# CNEPuckRevF_Drivers_2.net
KiCad netlist of a schematic drawn in Altium Designer
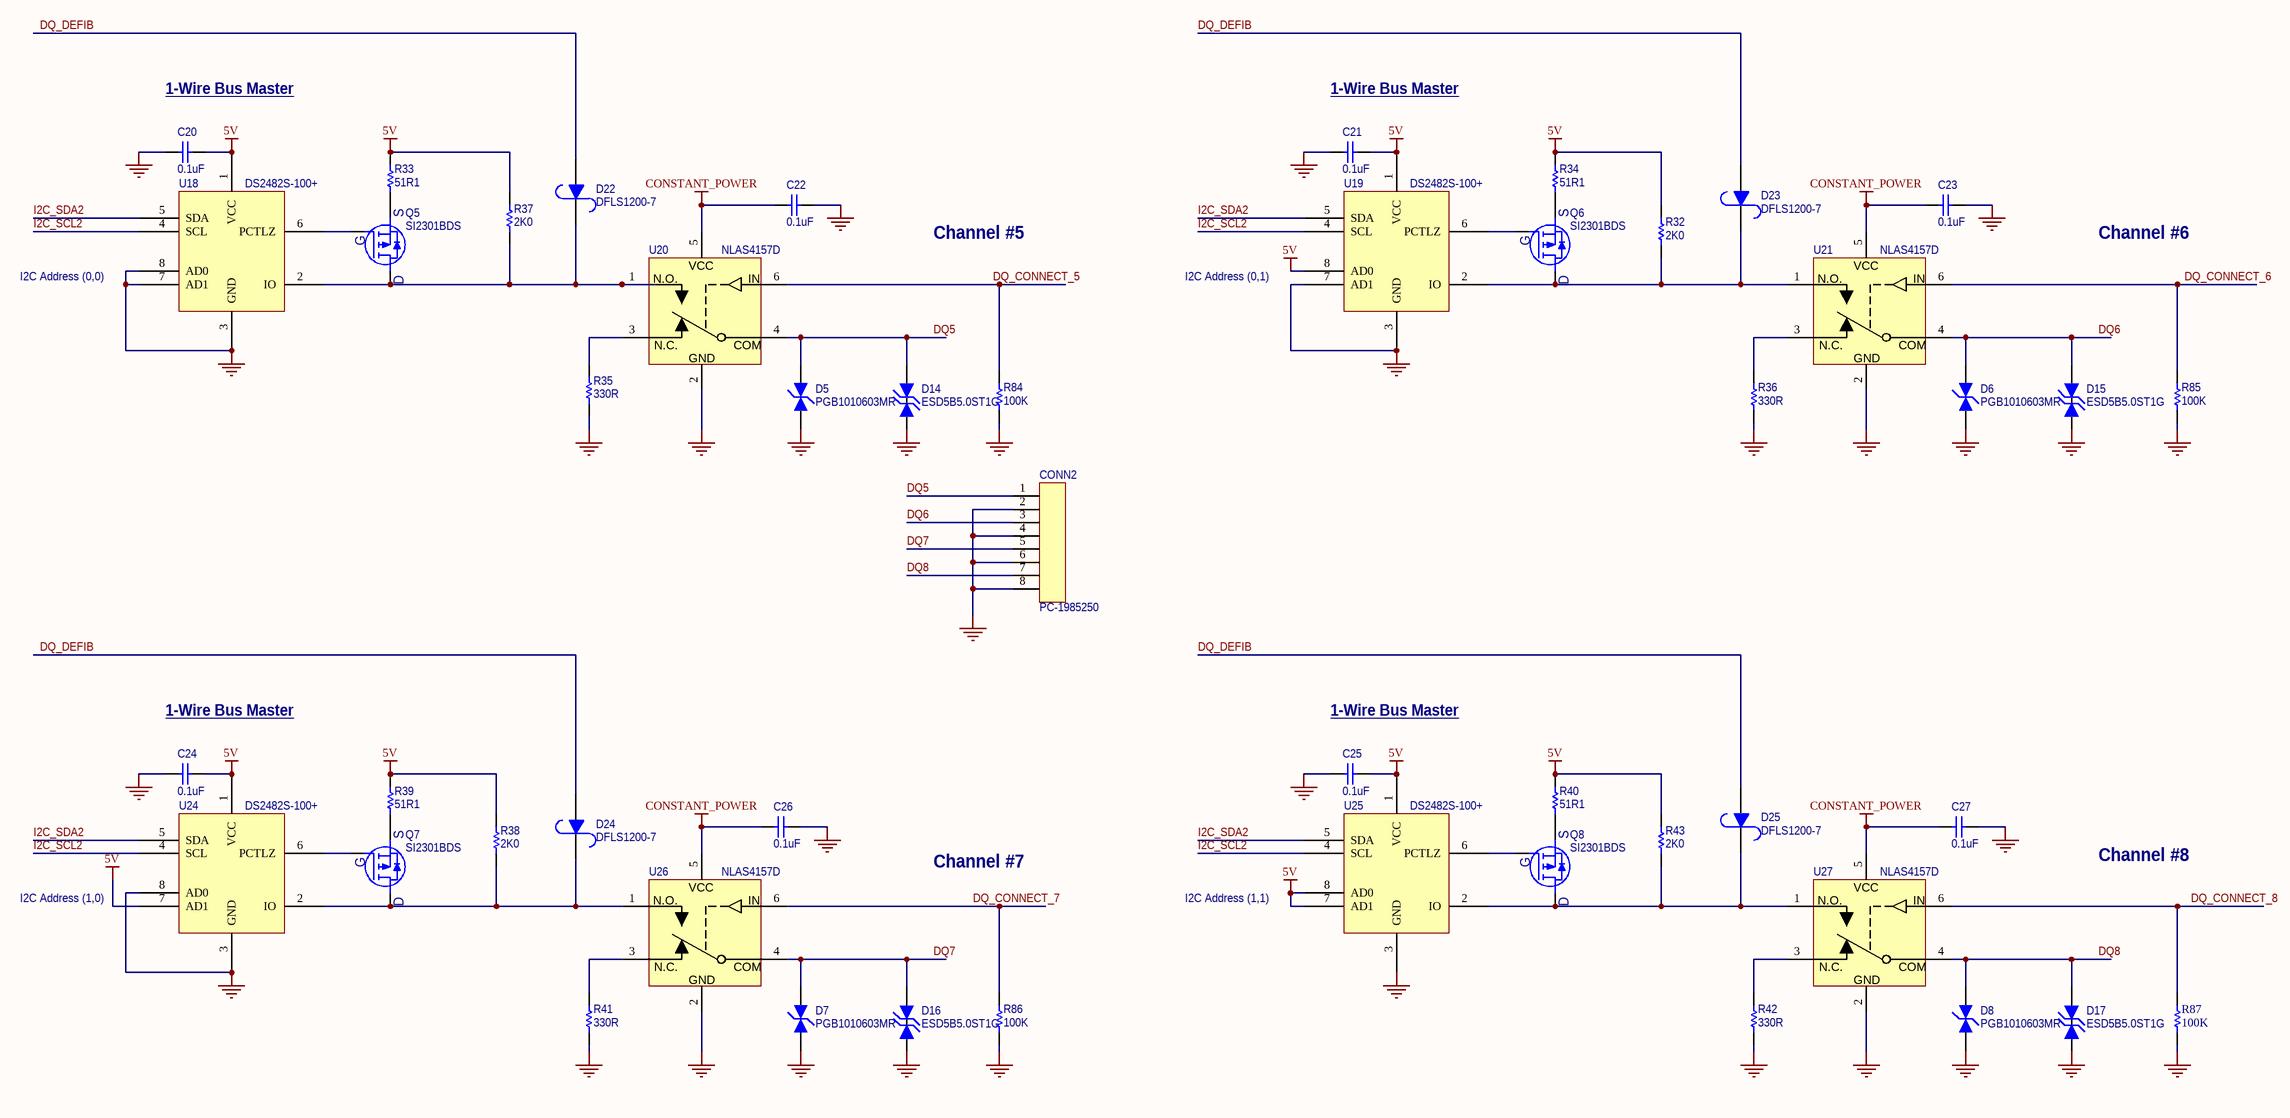
[diagram p0: CNEPuckRevF_Drivers_2.SchDoc]

(export (version "E")
  (design (tool "Eeschema 10.0.6"))
  (components
    (comp (ref "C20")
      (value "0.1uF")
      (footprint "RC0603")
      (description "CAP CERM .1UF 10% 16V X7R 0603")
      (fields (field (name "TOLERANCE") "±10%") (field (name "MANUFACTURER PART NUMBER") "0603YC104KAT2A"))
      (libsource (lib "Swage") (part "0603YC104KAT2A"))
    )
    (comp (ref "C21")
      (value "0.1uF")
      (footprint "RC0603")
      (description "CAP CERM .1UF 10% 16V X7R 0603")
      (fields (field (name "TOLERANCE") "±10%") (field (name "MANUFACTURER PART NUMBER") "0603YC104KAT2A"))
      (libsource (lib "Swage") (part "0603YC104KAT2A"))
    )
    (comp (ref "C22")
      (value "0.1uF")
      (footprint "RC0603")
      (description "CAP CERM .1UF 10% 16V X7R 0603")
      (fields (field (name "TOLERANCE") "±10%") (field (name "MANUFACTURER PART NUMBER") "0603YC104KAT2A"))
      (libsource (lib "Swage") (part "0603YC104KAT2A"))
    )
    (comp (ref "C23")
      (value "0.1uF")
      (footprint "RC0603")
      (description "CAP CERM .1UF 10% 16V X7R 0603")
      (fields (field (name "TOLERANCE") "±10%") (field (name "MANUFACTURER PART NUMBER") "0603YC104KAT2A"))
      (libsource (lib "Swage") (part "0603YC104KAT2A"))
    )
    (comp (ref "C24")
      (value "0.1uF")
      (footprint "RC0603")
      (description "CAP CERM .1UF 10% 16V X7R 0603")
      (fields (field (name "TOLERANCE") "±10%") (field (name "MANUFACTURER PART NUMBER") "0603YC104KAT2A"))
      (libsource (lib "Swage") (part "0603YC104KAT2A"))
    )
    (comp (ref "C25")
      (value "0.1uF")
      (footprint "RC0603")
      (description "CAP CERM .1UF 10% 16V X7R 0603")
      (fields (field (name "TOLERANCE") "±10%") (field (name "MANUFACTURER PART NUMBER") "0603YC104KAT2A"))
      (libsource (lib "Swage") (part "0603YC104KAT2A"))
    )
    (comp (ref "C26")
      (value "0.1uF")
      (footprint "RC0603")
      (description "CAP CERM .1UF 10% 16V X7R 0603")
      (fields (field (name "TOLERANCE") "±10%") (field (name "MANUFACTURER PART NUMBER") "0603YC104KAT2A"))
      (libsource (lib "Swage") (part "0603YC104KAT2A"))
    )
    (comp (ref "C27")
      (value "0.1uF")
      (footprint "RC0603")
      (description "CAP CERM .1UF 10% 16V X7R 0603")
      (fields (field (name "TOLERANCE") "±10%") (field (name "MANUFACTURER PART NUMBER") "0603YC104KAT2A"))
      (libsource (lib "Swage") (part "0603YC104KAT2A"))
    )
    (comp (ref "CONN2")
      (value "PC-1985250")
      (footprint "PTSA1.5/8-3.5-Z")
      (description "TERM BLOCK PCB 8POS 3.5MM GREEN")
      (fields
        (field (name "MANUFACTURER") "Phoenix Contact")
        (field (name "MANUFACTURER PART NUMBER") "1985250")
      )
      (libsource (lib "Swage") (part "1985250"))
    )
    (comp (ref "D5")
      (value "PGB1010603MR")
      (footprint "RC0603")
      (description "SUPPRESSOR ESD 24VDC 0603 SMD")
      (fields (field (name "MANUFACTURER") "Littelfuse Inc"))
      (libsource (lib "Swage") (part "PGB1010603MR"))
    )
    (comp (ref "D6")
      (value "PGB1010603MR")
      (footprint "RC0603")
      (description "SUPPRESSOR ESD 24VDC 0603 SMD")
      (fields (field (name "MANUFACTURER") "Littelfuse Inc"))
      (libsource (lib "Swage") (part "PGB1010603MR"))
    )
    (comp (ref "D7")
      (value "PGB1010603MR")
      (footprint "RC0603")
      (description "SUPPRESSOR ESD 24VDC 0603 SMD")
      (fields (field (name "MANUFACTURER") "Littelfuse Inc"))
      (libsource (lib "Swage") (part "PGB1010603MR"))
    )
    (comp (ref "D8")
      (value "PGB1010603MR")
      (footprint "RC0603")
      (description "SUPPRESSOR ESD 24VDC 0603 SMD")
      (fields (field (name "MANUFACTURER") "Littelfuse Inc"))
      (libsource (lib "Swage") (part "PGB1010603MR"))
    )
    (comp (ref "D14")
      (value "ESD5B5.0ST1G")
      (footprint "SOD-523")
      (description "TVS BIDIRECT 50W SOD523")
      (fields (field (name "MANUFACTURER") "ON Semiconductor"))
      (libsource (lib "Swage") (part "ESD5B5.0ST1G"))
    )
    (comp (ref "D15")
      (value "ESD5B5.0ST1G")
      (footprint "SOD-523")
      (description "TVS BIDIRECT 50W SOD523")
      (fields (field (name "MANUFACTURER") "ON Semiconductor"))
      (libsource (lib "Swage") (part "ESD5B5.0ST1G"))
    )
    (comp (ref "D16")
      (value "ESD5B5.0ST1G")
      (footprint "SOD-523")
      (description "TVS BIDIRECT 50W SOD523")
      (fields (field (name "MANUFACTURER") "ON Semiconductor"))
      (libsource (lib "Swage") (part "ESD5B5.0ST1G"))
    )
    (comp (ref "D17")
      (value "ESD5B5.0ST1G")
      (footprint "SOD-523")
      (description "TVS BIDIRECT 50W SOD523")
      (fields (field (name "MANUFACTURER") "ON Semiconductor"))
      (libsource (lib "Swage") (part "ESD5B5.0ST1G"))
    )
    (comp (ref "D22")
      (value "DFLS1200-7")
      (footprint "POWERDI-123")
      (description "DIODE SCHOTTKY 1A 200V PWRDI 123")
      (fields (field (name "MANUFACTURER") "Diodes Inc"))
      (libsource (lib "Swage") (part "DFLS1200-7"))
    )
    (comp (ref "D23")
      (value "DFLS1200-7")
      (footprint "POWERDI-123")
      (description "DIODE SCHOTTKY 1A 200V PWRDI 123")
      (fields (field (name "MANUFACTURER") "Diodes Inc"))
      (libsource (lib "Swage") (part "DFLS1200-7"))
    )
    (comp (ref "D24")
      (value "DFLS1200-7")
      (footprint "POWERDI-123")
      (description "DIODE SCHOTTKY 1A 200V PWRDI 123")
      (fields (field (name "MANUFACTURER") "Diodes Inc"))
      (libsource (lib "Swage") (part "DFLS1200-7"))
    )
    (comp (ref "D25")
      (value "DFLS1200-7")
      (footprint "POWERDI-123")
      (description "DIODE SCHOTTKY 1A 200V PWRDI 123")
      (fields (field (name "MANUFACTURER") "Diodes Inc"))
      (libsource (lib "Swage") (part "DFLS1200-7"))
    )
    (comp (ref "Q5")
      (value "SI2301BDS")
      (footprint "SOT23(DGS)")
      (description "MOSFET P-CH 20V 2.2A SOT23-3")
      (fields
        (field (name "MANUFACTURER") "Vishay/Siliconix")
        (field (name "MANUFACTURER PART NUMBER") "SI2301BDS-T1-E3")
      )
      (libsource (lib "Swage") (part "SI2301BDS-T1-E3"))
    )
    (comp (ref "Q6")
      (value "SI2301BDS")
      (footprint "SOT23(DGS)")
      (description "MOSFET P-CH 20V 2.2A SOT23-3")
      (fields
        (field (name "MANUFACTURER") "Vishay/Siliconix")
        (field (name "MANUFACTURER PART NUMBER") "SI2301BDS-T1-E3")
      )
      (libsource (lib "Swage") (part "SI2301BDS-T1-E3"))
    )
    (comp (ref "Q7")
      (value "SI2301BDS")
      (footprint "SOT23(DGS)")
      (description "MOSFET P-CH 20V 2.2A SOT23-3")
      (fields
        (field (name "MANUFACTURER") "Vishay/Siliconix")
        (field (name "MANUFACTURER PART NUMBER") "SI2301BDS-T1-E3")
      )
      (libsource (lib "Swage") (part "SI2301BDS-T1-E3"))
    )
    (comp (ref "Q8")
      (value "SI2301BDS")
      (footprint "SOT23(DGS)")
      (description "MOSFET P-CH 20V 2.2A SOT23-3")
      (fields
        (field (name "MANUFACTURER") "Vishay/Siliconix")
        (field (name "MANUFACTURER PART NUMBER") "SI2301BDS-T1-E3")
      )
      (libsource (lib "Swage") (part "SI2301BDS-T1-E3"))
    )
    (comp (ref "R32")
      (value "2K0")
      (footprint "RC0603")
      (description "RES 2K OHM 1/10W 1% 0603 SMD")
      (fields
        (field (name "MANUFACTURER") "Panasonic Electronic Components")
        (field (name "MANUFACTURER PART NUMBER") "ERJ-3EKF2001V")
      )
      (libsource (lib "Swage") (part "ERJ-3EKF2001V"))
    )
    (comp (ref "R33")
      (value "51R1")
      (footprint "RC0603")
      (description "RES 51.1 OHM .25W 1% 0603 SMD")
      (fields
        (field (name "MANUFACTURER") "Vishay Dale")
        (field (name "MANUFACTURER PART NUMBER") "CRCW060351R1FKEAHP")
      )
      (libsource (lib "Swage") (part "CRCW060351R1FKEAHP"))
    )
    (comp (ref "R34")
      (value "51R1")
      (footprint "RC0603")
      (description "RES 51.1 OHM .25W 1% 0603 SMD")
      (fields
        (field (name "MANUFACTURER") "Vishay Dale")
        (field (name "MANUFACTURER PART NUMBER") "CRCW060351R1FKEAHP")
      )
      (libsource (lib "Swage") (part "CRCW060351R1FKEAHP"))
    )
    (comp (ref "R35")
      (value "330R")
      (footprint "RC0805")
      (description "RES 330 OHM 1/8W 5% 0805 SMD")
      (fields
        (field (name "MANUFACTURER") "KOA Speer Technologies")
        (field (name "MANUFACTURER PART NUMBER") "RK73B2ATTD331J")
      )
      (libsource (lib "Swage") (part "ERJ-6GEYJ331V"))
    )
    (comp (ref "R36")
      (value "330R")
      (footprint "RC0805")
      (description "RES 330 OHM 1/8W 5% 0805 SMD")
      (fields
        (field (name "MANUFACTURER") "KOA Speer Technologies")
        (field (name "MANUFACTURER PART NUMBER") "RK73B2ATTD331J")
      )
      (libsource (lib "Swage") (part "ERJ-6GEYJ331V"))
    )
    (comp (ref "R37")
      (value "2K0")
      (footprint "RC0603")
      (description "RES 2K OHM 1/10W 1% 0603 SMD")
      (fields
        (field (name "MANUFACTURER") "Panasonic Electronic Components")
        (field (name "MANUFACTURER PART NUMBER") "ERJ-3EKF2001V")
      )
      (libsource (lib "Swage") (part "ERJ-3EKF2001V"))
    )
    (comp (ref "R38")
      (value "2K0")
      (footprint "RC0603")
      (description "RES 2K OHM 1/10W 1% 0603 SMD")
      (fields
        (field (name "MANUFACTURER") "Panasonic Electronic Components")
        (field (name "MANUFACTURER PART NUMBER") "ERJ-3EKF2001V")
      )
      (libsource (lib "Swage") (part "ERJ-3EKF2001V"))
    )
    (comp (ref "R39")
      (value "51R1")
      (footprint "RC0603")
      (description "RES 51.1 OHM .25W 1% 0603 SMD")
      (fields
        (field (name "MANUFACTURER") "Vishay Dale")
        (field (name "MANUFACTURER PART NUMBER") "CRCW060351R1FKEAHP")
      )
      (libsource (lib "Swage") (part "CRCW060351R1FKEAHP"))
    )
    (comp (ref "R40")
      (value "51R1")
      (footprint "RC0603")
      (description "RES 51.1 OHM .25W 1% 0603 SMD")
      (fields
        (field (name "MANUFACTURER") "Vishay Dale")
        (field (name "MANUFACTURER PART NUMBER") "CRCW060351R1FKEAHP")
      )
      (libsource (lib "Swage") (part "CRCW060351R1FKEAHP"))
    )
    (comp (ref "R41")
      (value "330R")
      (footprint "RC0805")
      (description "RES 330 OHM 1/8W 5% 0805 SMD")
      (fields
        (field (name "MANUFACTURER") "KOA Speer Technologies")
        (field (name "MANUFACTURER PART NUMBER") "RK73B2ATTD331J")
      )
      (libsource (lib "Swage") (part "ERJ-6GEYJ331V"))
    )
    (comp (ref "R42")
      (value "330R")
      (footprint "RC0805")
      (description "RES 330 OHM 1/8W 5% 0805 SMD")
      (fields
        (field (name "MANUFACTURER") "KOA Speer Technologies")
        (field (name "MANUFACTURER PART NUMBER") "RK73B2ATTD331J")
      )
      (libsource (lib "Swage") (part "ERJ-6GEYJ331V"))
    )
    (comp (ref "R43")
      (value "2K0")
      (footprint "RC0603")
      (description "RES 2K OHM 1/10W 1% 0603 SMD")
      (fields
        (field (name "MANUFACTURER") "Panasonic Electronic Components")
        (field (name "MANUFACTURER PART NUMBER") "ERJ-3EKF2001V")
      )
      (libsource (lib "Swage") (part "ERJ-3EKF2001V"))
    )
    (comp (ref "R84")
      (value "100K")
      (footprint "RC0603")
      (description "RES 100K OHM 1/10W 5% 0603 SMD")
      (fields
        (field (name "MANUFACTURER") "Panasonic Electronic Components")
        (field (name "MANUFACTURER PART NUMBER") "ERJ-3GEYJ104V")
      )
      (libsource (lib "Swage") (part "ERJ-3GEYJ104V"))
    )
    (comp (ref "R85")
      (value "100K")
      (footprint "RC0603")
      (description "RES 100K OHM 1/10W 5% 0603 SMD")
      (fields
        (field (name "MANUFACTURER") "Panasonic Electronic Components")
        (field (name "MANUFACTURER PART NUMBER") "ERJ-3GEYJ104V")
      )
      (libsource (lib "Swage") (part "ERJ-3GEYJ104V"))
    )
    (comp (ref "R86")
      (value "100K")
      (footprint "RC0603")
      (description "RES 100K OHM 1/10W 5% 0603 SMD")
      (fields
        (field (name "MANUFACTURER") "Panasonic Electronic Components")
        (field (name "MANUFACTURER PART NUMBER") "ERJ-3GEYJ104V")
      )
      (libsource (lib "Swage") (part "ERJ-3GEYJ104V"))
    )
    (comp (ref "R87")
      (value "100K")
      (footprint "RC0603")
      (description "RES 100K OHM 1/10W 5% 0603 SMD")
      (fields
        (field (name "MANUFACTURER") "Panasonic Electronic Components")
        (field (name "MANUFACTURER PART NUMBER") "ERJ-3GEYJ104V")
      )
      (libsource (lib "Swage") (part "ERJ-3GEYJ104V"))
    )
    (comp (ref "U18")
      (value "DS2482S-100+")
      (footprint "SOIC127P580X153-8N")
      (description "IC BRIDGE I2C TO 1-WIRE 8-SOIC")
      (fields (field (name "MANUFACTURER") "Maxim Integrated"))
      (libsource (lib "Swage") (part "DS2482S-100+"))
    )
    (comp (ref "U19")
      (value "DS2482S-100+")
      (footprint "SOIC127P580X153-8N")
      (description "IC BRIDGE I2C TO 1-WIRE 8-SOIC")
      (fields (field (name "MANUFACTURER") "Maxim Integrated"))
      (libsource (lib "Swage") (part "DS2482S-100+"))
    )
    (comp (ref "U20")
      (value "NLAS4157D")
      (footprint "TS5A3160")
      (description "IC SWITCH SPDT SC88")
      (fields
        (field (name "MANUFACTURER") "ON Semiconductor")
        (field (name "MANUFACTURER PART NUMBER") "NLAS4157DFT2G")
      )
      (libsource (lib "Swage") (part "NLAS4157DFT2G"))
    )
    (comp (ref "U21")
      (value "NLAS4157D")
      (footprint "TS5A3160")
      (description "IC SWITCH SPDT SC88")
      (fields
        (field (name "MANUFACTURER") "ON Semiconductor")
        (field (name "MANUFACTURER PART NUMBER") "NLAS4157DFT2G")
      )
      (libsource (lib "Swage") (part "NLAS4157DFT2G"))
    )
    (comp (ref "U24")
      (value "DS2482S-100+")
      (footprint "SOIC127P580X153-8N")
      (description "IC BRIDGE I2C TO 1-WIRE 8-SOIC")
      (fields (field (name "MANUFACTURER") "Maxim Integrated"))
      (libsource (lib "Swage") (part "DS2482S-100+"))
    )
    (comp (ref "U25")
      (value "DS2482S-100+")
      (footprint "SOIC127P580X153-8N")
      (description "IC BRIDGE I2C TO 1-WIRE 8-SOIC")
      (fields (field (name "MANUFACTURER") "Maxim Integrated"))
      (libsource (lib "Swage") (part "DS2482S-100+"))
    )
    (comp (ref "U26")
      (value "NLAS4157D")
      (footprint "TS5A3160")
      (description "IC SWITCH SPDT SC88")
      (fields
        (field (name "MANUFACTURER") "ON Semiconductor")
        (field (name "MANUFACTURER PART NUMBER") "NLAS4157DFT2G")
      )
      (libsource (lib "Swage") (part "NLAS4157DFT2G"))
    )
    (comp (ref "U27")
      (value "NLAS4157D")
      (footprint "TS5A3160")
      (description "IC SWITCH SPDT SC88")
      (fields
        (field (name "MANUFACTURER") "ON Semiconductor")
        (field (name "MANUFACTURER PART NUMBER") "NLAS4157DFT2G")
      )
      (libsource (lib "Swage") (part "NLAS4157DFT2G"))
    )
  )
  (nets
    (net (code "1") (name "/DQ5") (class "Default")
      (node (ref "CONN2") (pin "1") (pinfunction "1_1") (pintype "passive"))
      (node (ref "D14") (pin "2") (pinfunction "2_2") (pintype "passive"))
      (node (ref "D5") (pin "2") (pinfunction "2_2") (pintype "passive"))
      (node (ref "U20") (pin "4") (pinfunction "4_4") (pintype "passive"))
    )
    (net (code "2") (name "/DQ6") (class "Default")
      (node (ref "CONN2") (pin "3") (pinfunction "3_3") (pintype "passive"))
      (node (ref "D15") (pin "2") (pinfunction "2_2") (pintype "passive"))
      (node (ref "D6") (pin "2") (pinfunction "2_2") (pintype "passive"))
      (node (ref "U21") (pin "4") (pinfunction "4_4") (pintype "passive"))
    )
    (net (code "3") (name "/DQ7") (class "Default")
      (node (ref "CONN2") (pin "5") (pinfunction "5_5") (pintype "passive"))
      (node (ref "D16") (pin "2") (pinfunction "2_2") (pintype "passive"))
      (node (ref "D7") (pin "2") (pinfunction "2_2") (pintype "passive"))
      (node (ref "U26") (pin "4") (pinfunction "4_4") (pintype "passive"))
    )
    (net (code "4") (name "/DQ8") (class "Default")
      (node (ref "CONN2") (pin "7") (pinfunction "7_7") (pintype "passive"))
      (node (ref "D17") (pin "2") (pinfunction "2_2") (pintype "passive"))
      (node (ref "D8") (pin "2") (pinfunction "2_2") (pintype "passive"))
      (node (ref "U27") (pin "4") (pinfunction "4_4") (pintype "passive"))
    )
    (net (code "5") (name "/DQ_CONNECT_5") (class "Default")
      (node (ref "R84") (pin "1") (pinfunction "1_1") (pintype "passive"))
      (node (ref "U20") (pin "6") (pinfunction "6_6") (pintype "passive"))
    )
    (net (code "6") (name "/DQ_CONNECT_6") (class "Default")
      (node (ref "R85") (pin "1") (pinfunction "1_1") (pintype "passive"))
      (node (ref "U21") (pin "6") (pinfunction "6_6") (pintype "passive"))
    )
    (net (code "7") (name "/DQ_CONNECT_7") (class "Default")
      (node (ref "R86") (pin "1") (pinfunction "1_1") (pintype "passive"))
      (node (ref "U26") (pin "6") (pinfunction "6_6") (pintype "passive"))
    )
    (net (code "8") (name "/DQ_CONNECT_8") (class "Default")
      (node (ref "R87") (pin "1") (pinfunction "1_1") (pintype "passive"))
      (node (ref "U27") (pin "6") (pinfunction "6_6") (pintype "passive"))
    )
    (net (code "9") (name "/DQ_DEFIB") (class "Default")
      (node (ref "D22") (pin "1") (pinfunction "A_1") (pintype "passive"))
      (node (ref "D23") (pin "1") (pinfunction "A_1") (pintype "passive"))
      (node (ref "D24") (pin "1") (pinfunction "A_1") (pintype "passive"))
      (node (ref "D25") (pin "1") (pinfunction "A_1") (pintype "passive"))
    )
    (net (code "10") (name "/I2C_SCL2") (class "Default")
      (node (ref "U18") (pin "4") (pinfunction "SCL_4") (pintype "passive"))
      (node (ref "U19") (pin "4") (pinfunction "SCL_4") (pintype "passive"))
      (node (ref "U24") (pin "4") (pinfunction "SCL_4") (pintype "passive"))
      (node (ref "U25") (pin "4") (pinfunction "SCL_4") (pintype "passive"))
    )
    (net (code "11") (name "/I2C_SDA2") (class "Default")
      (node (ref "U18") (pin "5") (pinfunction "SDA_5") (pintype "passive"))
      (node (ref "U19") (pin "5") (pinfunction "SDA_5") (pintype "passive"))
      (node (ref "U24") (pin "5") (pinfunction "SDA_5") (pintype "passive"))
      (node (ref "U25") (pin "5") (pinfunction "SDA_5") (pintype "passive"))
    )
    (net (code "12") (name "5V") (class "Default")
      (node (ref "C20") (pin "2") (pinfunction "2_2") (pintype "passive"))
      (node (ref "C21") (pin "2") (pinfunction "2_2") (pintype "passive"))
      (node (ref "C24") (pin "2") (pinfunction "2_2") (pintype "passive"))
      (node (ref "C25") (pin "2") (pinfunction "2_2") (pintype "passive"))
      (node (ref "R32") (pin "1") (pinfunction "1_1") (pintype "passive"))
      (node (ref "R33") (pin "1") (pinfunction "1_1") (pintype "passive"))
      (node (ref "R34") (pin "1") (pinfunction "1_1") (pintype "passive"))
      (node (ref "R37") (pin "1") (pinfunction "1_1") (pintype "passive"))
      (node (ref "R38") (pin "1") (pinfunction "1_1") (pintype "passive"))
      (node (ref "R39") (pin "1") (pinfunction "1_1") (pintype "passive"))
      (node (ref "R40") (pin "1") (pinfunction "1_1") (pintype "passive"))
      (node (ref "R43") (pin "1") (pinfunction "1_1") (pintype "passive"))
      (node (ref "U18") (pin "1") (pinfunction "VCC_1") (pintype "passive"))
      (node (ref "U19") (pin "1") (pinfunction "VCC_1") (pintype "passive"))
      (node (ref "U19") (pin "8") (pinfunction "AD0_8") (pintype "passive"))
      (node (ref "U24") (pin "1") (pinfunction "VCC_1") (pintype "passive"))
      (node (ref "U24") (pin "7") (pinfunction "AD1_7") (pintype "passive"))
      (node (ref "U25") (pin "1") (pinfunction "VCC_1") (pintype "passive"))
      (node (ref "U25") (pin "7") (pinfunction "AD1_7") (pintype "passive"))
      (node (ref "U25") (pin "8") (pinfunction "AD0_8") (pintype "passive"))
    )
    (net (code "13") (name "CONSTANT_POWER") (class "Default")
      (node (ref "C22") (pin "1") (pinfunction "1_1") (pintype "passive"))
      (node (ref "C23") (pin "1") (pinfunction "1_1") (pintype "passive"))
      (node (ref "C26") (pin "1") (pinfunction "1_1") (pintype "passive"))
      (node (ref "C27") (pin "1") (pinfunction "1_1") (pintype "passive"))
      (node (ref "U20") (pin "5") (pinfunction "5_5") (pintype "passive"))
      (node (ref "U21") (pin "5") (pinfunction "5_5") (pintype "passive"))
      (node (ref "U26") (pin "5") (pinfunction "5_5") (pintype "passive"))
      (node (ref "U27") (pin "5") (pinfunction "5_5") (pintype "passive"))
    )
    (net (code "14") (name "GND") (class "Default")
      (node (ref "C20") (pin "1") (pinfunction "1_1") (pintype "passive"))
      (node (ref "C21") (pin "1") (pinfunction "1_1") (pintype "passive"))
      (node (ref "C22") (pin "2") (pinfunction "2_2") (pintype "passive"))
      (node (ref "C23") (pin "2") (pinfunction "2_2") (pintype "passive"))
      (node (ref "C24") (pin "1") (pinfunction "1_1") (pintype "passive"))
      (node (ref "C25") (pin "1") (pinfunction "1_1") (pintype "passive"))
      (node (ref "C26") (pin "2") (pinfunction "2_2") (pintype "passive"))
      (node (ref "C27") (pin "2") (pinfunction "2_2") (pintype "passive"))
      (node (ref "CONN2") (pin "2") (pinfunction "2_2") (pintype "passive"))
      (node (ref "CONN2") (pin "4") (pinfunction "4_4") (pintype "passive"))
      (node (ref "CONN2") (pin "6") (pinfunction "6_6") (pintype "passive"))
      (node (ref "CONN2") (pin "8") (pinfunction "8_8") (pintype "passive"))
      (node (ref "D14") (pin "1") (pintype "passive"))
      (node (ref "D15") (pin "1") (pintype "passive"))
      (node (ref "D16") (pin "1") (pintype "passive"))
      (node (ref "D17") (pin "1") (pintype "passive"))
      (node (ref "D5") (pin "1") (pintype "passive"))
      (node (ref "D6") (pin "1") (pintype "passive"))
      (node (ref "D7") (pin "1") (pintype "passive"))
      (node (ref "D8") (pin "1") (pintype "passive"))
      (node (ref "R35") (pin "2") (pinfunction "2_2") (pintype "passive"))
      (node (ref "R36") (pin "1") (pinfunction "1_1") (pintype "passive"))
      (node (ref "R41") (pin "2") (pinfunction "2_2") (pintype "passive"))
      (node (ref "R42") (pin "2") (pinfunction "2_2") (pintype "passive"))
      (node (ref "R84") (pin "2") (pinfunction "2_2") (pintype "passive"))
      (node (ref "R85") (pin "2") (pinfunction "2_2") (pintype "passive"))
      (node (ref "R86") (pin "2") (pinfunction "2_2") (pintype "passive"))
      (node (ref "R87") (pin "2") (pinfunction "2_2") (pintype "passive"))
      (node (ref "U18") (pin "3") (pinfunction "GND_3") (pintype "passive"))
      (node (ref "U18") (pin "7") (pinfunction "AD1_7") (pintype "passive"))
      (node (ref "U18") (pin "8") (pinfunction "AD0_8") (pintype "passive"))
      (node (ref "U19") (pin "3") (pinfunction "GND_3") (pintype "passive"))
      (node (ref "U19") (pin "7") (pinfunction "AD1_7") (pintype "passive"))
      (node (ref "U20") (pin "2") (pinfunction "GND_2") (pintype "passive"))
      (node (ref "U21") (pin "2") (pinfunction "GND_2") (pintype "passive"))
      (node (ref "U24") (pin "3") (pinfunction "GND_3") (pintype "passive"))
      (node (ref "U24") (pin "8") (pinfunction "AD0_8") (pintype "passive"))
      (node (ref "U25") (pin "3") (pinfunction "GND_3") (pintype "passive"))
      (node (ref "U26") (pin "2") (pinfunction "GND_2") (pintype "passive"))
      (node (ref "U27") (pin "2") (pinfunction "GND_2") (pintype "passive"))
    )
    (net (code "15") (name "Net-(D22-K)") (class "Default")
      (node (ref "D22") (pin "2") (pinfunction "K_2") (pintype "passive"))
      (node (ref "Q5") (pin "D") (pinfunction "D_D") (pintype "passive"))
      (node (ref "R37") (pin "2") (pinfunction "2_2") (pintype "passive"))
      (node (ref "U18") (pin "2") (pinfunction "IO_2") (pintype "passive"))
      (node (ref "U20") (pin "1") (pinfunction "NO_1") (pintype "passive"))
    )
    (net (code "16") (name "Net-(D23-K)") (class "Default")
      (node (ref "D23") (pin "2") (pinfunction "K_2") (pintype "passive"))
      (node (ref "Q6") (pin "D") (pinfunction "D_D") (pintype "passive"))
      (node (ref "R32") (pin "2") (pinfunction "2_2") (pintype "passive"))
      (node (ref "U19") (pin "2") (pinfunction "IO_2") (pintype "passive"))
      (node (ref "U21") (pin "1") (pinfunction "NO_1") (pintype "passive"))
    )
    (net (code "17") (name "Net-(D24-K)") (class "Default")
      (node (ref "D24") (pin "2") (pinfunction "K_2") (pintype "passive"))
      (node (ref "Q7") (pin "D") (pinfunction "D_D") (pintype "passive"))
      (node (ref "R38") (pin "2") (pinfunction "2_2") (pintype "passive"))
      (node (ref "U24") (pin "2") (pinfunction "IO_2") (pintype "passive"))
      (node (ref "U26") (pin "1") (pinfunction "NO_1") (pintype "passive"))
    )
    (net (code "18") (name "Net-(D25-K)") (class "Default")
      (node (ref "D25") (pin "2") (pinfunction "K_2") (pintype "passive"))
      (node (ref "Q8") (pin "D") (pinfunction "D_D") (pintype "passive"))
      (node (ref "R43") (pin "2") (pinfunction "2_2") (pintype "passive"))
      (node (ref "U25") (pin "2") (pinfunction "IO_2") (pintype "passive"))
      (node (ref "U27") (pin "1") (pinfunction "NO_1") (pintype "passive"))
    )
    (net (code "19") (name "Net-(Q5-PadS)") (class "Default")
      (node (ref "Q5") (pin "S") (pinfunction "S_S") (pintype "passive"))
      (node (ref "R33") (pin "2") (pinfunction "2_2") (pintype "passive"))
    )
    (net (code "20") (name "Net-(Q6-PadS)") (class "Default")
      (node (ref "Q6") (pin "S") (pinfunction "S_S") (pintype "passive"))
      (node (ref "R34") (pin "2") (pinfunction "2_2") (pintype "passive"))
    )
    (net (code "21") (name "Net-(Q7-PadS)") (class "Default")
      (node (ref "Q7") (pin "S") (pinfunction "S_S") (pintype "passive"))
      (node (ref "R39") (pin "2") (pinfunction "2_2") (pintype "passive"))
    )
    (net (code "22") (name "Net-(Q8-PadS)") (class "Default")
      (node (ref "Q8") (pin "S") (pinfunction "S_S") (pintype "passive"))
      (node (ref "R40") (pin "2") (pinfunction "2_2") (pintype "passive"))
    )
    (net (code "23") (name "Net-(U18-PCTLZ)") (class "Default")
      (node (ref "Q5") (pin "G") (pinfunction "G_G") (pintype "passive"))
      (node (ref "U18") (pin "6") (pinfunction "PCTLZ_6") (pintype "passive"))
    )
    (net (code "24") (name "Net-(U19-PCTLZ)") (class "Default")
      (node (ref "Q6") (pin "G") (pinfunction "G_G") (pintype "passive"))
      (node (ref "U19") (pin "6") (pinfunction "PCTLZ_6") (pintype "passive"))
    )
    (net (code "25") (name "Net-(U20-NC)") (class "Default")
      (node (ref "R35") (pin "1") (pinfunction "1_1") (pintype "passive"))
      (node (ref "U20") (pin "3") (pinfunction "NC_3") (pintype "passive"))
    )
    (net (code "26") (name "Net-(U21-NC)") (class "Default")
      (node (ref "R36") (pin "2") (pinfunction "2_2") (pintype "passive"))
      (node (ref "U21") (pin "3") (pinfunction "NC_3") (pintype "passive"))
    )
    (net (code "27") (name "Net-(U24-PCTLZ)") (class "Default")
      (node (ref "Q7") (pin "G") (pinfunction "G_G") (pintype "passive"))
      (node (ref "U24") (pin "6") (pinfunction "PCTLZ_6") (pintype "passive"))
    )
    (net (code "28") (name "Net-(U25-PCTLZ)") (class "Default")
      (node (ref "Q8") (pin "G") (pinfunction "G_G") (pintype "passive"))
      (node (ref "U25") (pin "6") (pinfunction "PCTLZ_6") (pintype "passive"))
    )
    (net (code "29") (name "Net-(U26-NC)") (class "Default")
      (node (ref "R41") (pin "1") (pinfunction "1_1") (pintype "passive"))
      (node (ref "U26") (pin "3") (pinfunction "NC_3") (pintype "passive"))
    )
    (net (code "30") (name "Net-(U27-NC)") (class "Default")
      (node (ref "R42") (pin "1") (pinfunction "1_1") (pintype "passive"))
      (node (ref "U27") (pin "3") (pinfunction "NC_3") (pintype "passive"))
    )
  )
)
